# Low_Current_LED_Driver.net
KiCad netlist of a schematic drawn in Altium Designer
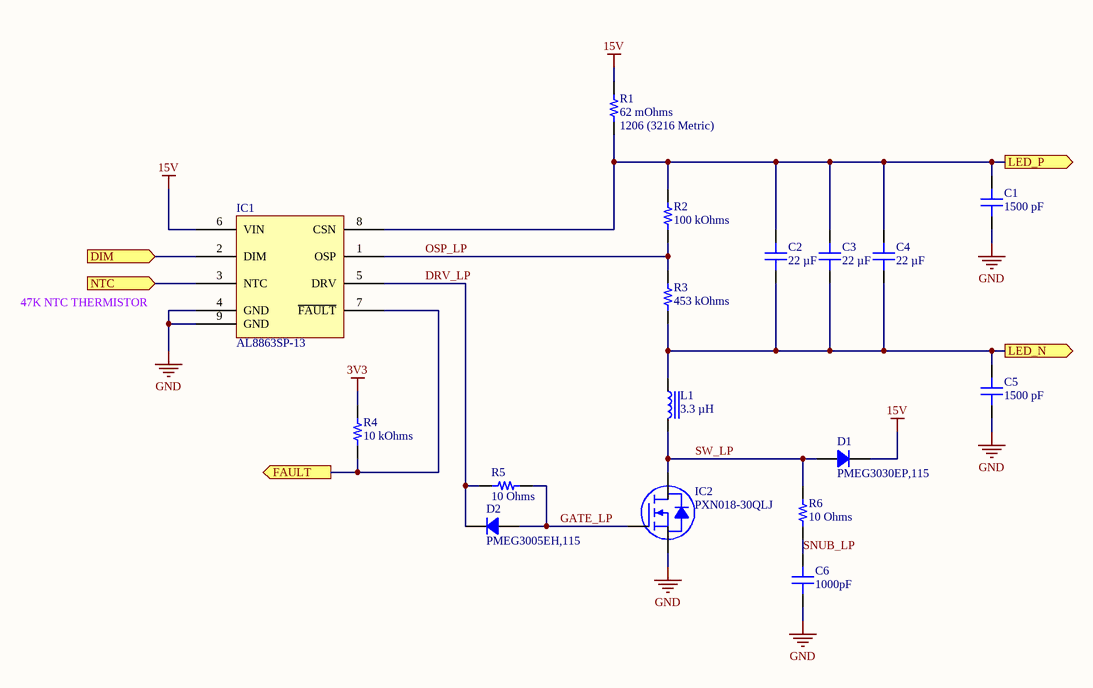
[diagram p0: Low Current LED Driver.SchDoc]

(export (version "E")
  (design (tool "Eeschema 10.0.6"))
  (components
    (comp (ref "C1")
      (value "1500 pF")
      (footprint "CAP 0603_1608")
      (description "CAP CER 1500PF 50V C0G/NP0 0603")
      (fields
        (field (name "PART NUMBER") "0603N152J500CT")
        (field (name "MANUFACTURER") "Walsin Technology Corporation")
      )
      (libsource (lib "altiumlibrary.com") (part "Capacitor"))
    )
    (comp (ref "C2")
      (value "22 µF")
      (footprint "CAP 1210_3225 - 1MM")
      (description "CAP CER 22UF 25V X5R 1210")
      (fields
        (field (name "PART NUMBER") "CL32A226KAJNNNE")
        (field (name "MANUFACTURER") "Samsung Electro-Mechanics")
      )
      (libsource (lib "altiumlibrary.com") (part "Capacitor"))
    )
    (comp (ref "C3")
      (value "22 µF")
      (footprint "CAP 1210_3225 - 1MM")
      (description "CAP CER 22UF 25V X5R 1210")
      (fields
        (field (name "PART NUMBER") "CL32A226KAJNNNE")
        (field (name "MANUFACTURER") "Samsung Electro-Mechanics")
      )
      (libsource (lib "altiumlibrary.com") (part "Capacitor"))
    )
    (comp (ref "C4")
      (value "22 µF")
      (footprint "CAP 1210_3225 - 1MM")
      (description "CAP CER 22UF 25V X5R 1210")
      (fields
        (field (name "PART NUMBER") "CL32A226KAJNNNE")
        (field (name "MANUFACTURER") "Samsung Electro-Mechanics")
      )
      (libsource (lib "altiumlibrary.com") (part "Capacitor"))
    )
    (comp (ref "C5")
      (value "1500 pF")
      (footprint "CAP 0603_1608")
      (description "CAP CER 1500PF 50V C0G/NP0 0603")
      (fields
        (field (name "PART NUMBER") "0603N152J500CT")
        (field (name "MANUFACTURER") "Walsin Technology Corporation")
      )
      (libsource (lib "altiumlibrary.com") (part "Capacitor"))
    )
    (comp (ref "C6")
      (value "1000pF")
      (footprint "CAP 0603_1608")
      (description "CAP CER 1000PF 50V X7R 0603")
      (fields (field (name "PART NUMBER") "06035C102KAT2A") (field (name "MANUFACTURER") "AVX Corporation"))
      (libsource (lib "altiumlibrary.com") (part "Capacitor"))
    )
    (comp (ref "D1")
      (value "PMEG3030EP,115")
      (footprint "NEXPERIA SOD-128 CFP5")
      (description "DIODE SCHOTTKY 30V 3A CFP5")
      (fields (field (name "MANUFACTURER") "Nexperia USA Inc."))
      (libsource (lib "altiumlibrary.com") (part "Diode"))
    )
    (comp (ref "D2")
      (value "PMEG3005EH,115")
      (footprint "SOD123F")
      (description "DIODE SCHOTTKY 30V 500MA SOD123F")
      (fields (field (name "MANUFACTURER") "Nexperia USA Inc."))
      (libsource (lib "altiumlibrary.com") (part "Diode"))
    )
    (comp (ref "IC1")
      (value "AL8863SP-13")
      (footprint "DIODES INC SO-8EP")
      (description "LED MV INT SWITCH SO-8EP")
      (fields (field (name "MANUFACTURER") "Diodes Incorporated"))
      (libsource (lib "altiumlibrary.com") (part "DIODES INC AL8863"))
    )
    (comp (ref "IC2")
      (value "PXN018-30QLJ")
      (footprint "NEXPERIA MLPAK33 SOT8002-1")
      (description "PXN018-30QL/SOT8002/MLPAK33")
      (fields (field (name "MANUFACTURER") "Nexperia USA Inc."))
      (libsource (lib "altiumlibrary.com") (part "NEXPERIA PXN MLPAK33 MOSFET N-CH"))
    )
    (comp (ref "L1")
      (value "3.3 µH")
      (footprint "TAIYO YUDEN NRS8030")
      (description "FIXED IND 3.3UH 4.3A 19 MOHM SMD")
      (fields (field (name "PART NUMBER") "NRS8030T3R3MJGJ") (field (name "MANUFACTURER") "Taiyo Yuden"))
      (libsource (lib "altiumlibrary.com") (part "Inductor"))
    )
    (comp (ref "R1")
      (value "62 mOhms")
      (footprint "STACKPOLE CSR1206")
      (description "RES 0.062 OHM 1% 1/2W 1206")
      (fields
        (field (name "PART NUMBER") "RLP73N2BR062FTDF")
        (field (name "PACKAGE / CASE") "1206 (3216 Metric)")
        (field (name "MANUFACTURER") "TE Connectivity Passive Product")
      )
      (libsource (lib "altiumlibrary.com") (part "Resistor"))
    )
    (comp (ref "R2")
      (value "100 kOhms")
      (footprint "RES 0603_1608")
      (description "RES 100K OHM 1% 1/10W 0603")
      (fields (field (name "PART NUMBER") "CRCW0603100KFKEAC") (field (name "MANUFACTURER") "Vishay Dale"))
      (libsource (lib "altiumlibrary.com") (part "Resistor"))
    )
    (comp (ref "R3")
      (value "453 kOhms")
      (footprint "RES 0603_1608")
      (description "RES 453K OHM 1% 1/10W 0603")
      (fields
        (field (name "PART NUMBER") "RMCF0603FT453K")
        (field (name "MANUFACTURER") "Stackpole Electronics Inc")
      )
      (libsource (lib "altiumlibrary.com") (part "Resistor"))
    )
    (comp (ref "R4")
      (value "10 kOhms")
      (footprint "RES 0603_1608")
      (description "RES SMD 10K OHM 5% 1/10W 0603")
      (fields
        (field (name "PART NUMBER") "ERJ-3GEYJ103V")
        (field (name "MANUFACTURER") "Panasonic Electronic Components")
      )
      (libsource (lib "altiumlibrary.com") (part "Resistor"))
    )
    (comp (ref "R5")
      (value "10 Ohms")
      (footprint "RES 0805_2012")
      (description "RES 10 OHM 5% 1/8W 0805")
      (fields (field (name "PART NUMBER") "CRCW080510R0JNEAC") (field (name "MANUFACTURER") "Vishay Dale"))
      (libsource (lib "altiumlibrary.com") (part "Resistor"))
    )
    (comp (ref "R6")
      (value "10 Ohms")
      (footprint "RES 0805_2012")
      (description "RES 10 OHM 5% 1/8W 0805")
      (fields (field (name "PART NUMBER") "CRCW080510R0JNEAC") (field (name "MANUFACTURER") "Vishay Dale"))
      (libsource (lib "altiumlibrary.com") (part "Resistor"))
    )
  )
  (nets
    (net (code "1") (name "/DIM") (class "Default")
      (node (ref "IC1") (pin "2") (pinfunction "DIM_2") (pintype "passive"))
    )
    (net (code "2") (name "/DRV_LP") (class "Default")
      (node (ref "D2") (pin "2") (pinfunction "2_2") (pintype "passive"))
      (node (ref "IC1") (pin "5") (pinfunction "DRV_5") (pintype "passive"))
      (node (ref "R5") (pin "1") (pinfunction "1_1") (pintype "passive"))
    )
    (net (code "3") (name "/FAULT") (class "Default")
      (node (ref "IC1") (pin "7") (pinfunction "~{FAULT}_7") (pintype "passive"))
      (node (ref "R4") (pin "1") (pinfunction "1_1") (pintype "passive"))
    )
    (net (code "4") (name "/GATE_LP") (class "Default")
      (node (ref "D2") (pin "1") (pinfunction "1_1") (pintype "passive"))
      (node (ref "IC2") (pin "G") (pinfunction "G_G") (pintype "passive"))
      (node (ref "R5") (pin "2") (pinfunction "2_2") (pintype "passive"))
    )
    (net (code "5") (name "/LED_N") (class "Default")
      (node (ref "C2") (pin "1") (pinfunction "1_1") (pintype "passive"))
      (node (ref "C3") (pin "1") (pinfunction "1_1") (pintype "passive"))
      (node (ref "C4") (pin "1") (pinfunction "1_1") (pintype "passive"))
      (node (ref "C5") (pin "2") (pinfunction "2_2") (pintype "passive"))
      (node (ref "L1") (pin "2") (pinfunction "2_2") (pintype "passive"))
      (node (ref "R3") (pin "1") (pinfunction "1_1") (pintype "passive"))
    )
    (net (code "6") (name "/LED_P") (class "Default")
      (node (ref "C1") (pin "2") (pinfunction "2_2") (pintype "passive"))
      (node (ref "C2") (pin "2") (pinfunction "2_2") (pintype "passive"))
      (node (ref "C3") (pin "2") (pinfunction "2_2") (pintype "passive"))
      (node (ref "C4") (pin "2") (pinfunction "2_2") (pintype "passive"))
      (node (ref "IC1") (pin "8") (pinfunction "CSN_8") (pintype "passive"))
      (node (ref "R1") (pin "1") (pinfunction "1_1") (pintype "passive"))
      (node (ref "R2") (pin "2") (pinfunction "2_2") (pintype "passive"))
    )
    (net (code "7") (name "/NTC") (class "Default")
      (node (ref "IC1") (pin "3") (pinfunction "NTC_3") (pintype "passive"))
    )
    (net (code "8") (name "/OSP_LP") (class "Default")
      (node (ref "IC1") (pin "1") (pinfunction "OSP_1") (pintype "passive"))
      (node (ref "R2") (pin "1") (pinfunction "1_1") (pintype "passive"))
      (node (ref "R3") (pin "2") (pinfunction "2_2") (pintype "passive"))
    )
    (net (code "9") (name "/SNUB_LP") (class "Default")
      (node (ref "C6") (pin "2") (pinfunction "2_2") (pintype "passive"))
      (node (ref "R6") (pin "1") (pinfunction "1_1") (pintype "passive"))
    )
    (net (code "10") (name "/SW_LP") (class "Default")
      (node (ref "D1") (pin "1") (pinfunction "1_1") (pintype "passive"))
      (node (ref "IC2") (pin "D") (pinfunction "D_D") (pintype "passive"))
      (node (ref "L1") (pin "1") (pinfunction "1_1") (pintype "passive"))
      (node (ref "R6") (pin "2") (pinfunction "2_2") (pintype "passive"))
    )
    (net (code "11") (name "3V3") (class "Default")
      (node (ref "R4") (pin "2") (pinfunction "2_2") (pintype "passive"))
    )
    (net (code "12") (name "15V") (class "Default")
      (node (ref "D1") (pin "2") (pinfunction "2_2") (pintype "passive"))
      (node (ref "IC1") (pin "6") (pinfunction "VIN_6") (pintype "passive"))
      (node (ref "R1") (pin "2") (pinfunction "2_2") (pintype "passive"))
    )
    (net (code "13") (name "GND") (class "Default")
      (node (ref "C1") (pin "1") (pinfunction "1_1") (pintype "passive"))
      (node (ref "C5") (pin "1") (pinfunction "1_1") (pintype "passive"))
      (node (ref "C6") (pin "1") (pinfunction "1_1") (pintype "passive"))
      (node (ref "IC1") (pin "4") (pinfunction "GND_4") (pintype "passive"))
      (node (ref "IC1") (pin "9") (pinfunction "GND_9") (pintype "passive"))
      (node (ref "IC2") (pin "S") (pinfunction "S_S") (pintype "passive"))
    )
  )
)
